# mainBoard.net
KiCad netlist of a schematic drawn in EAGLE
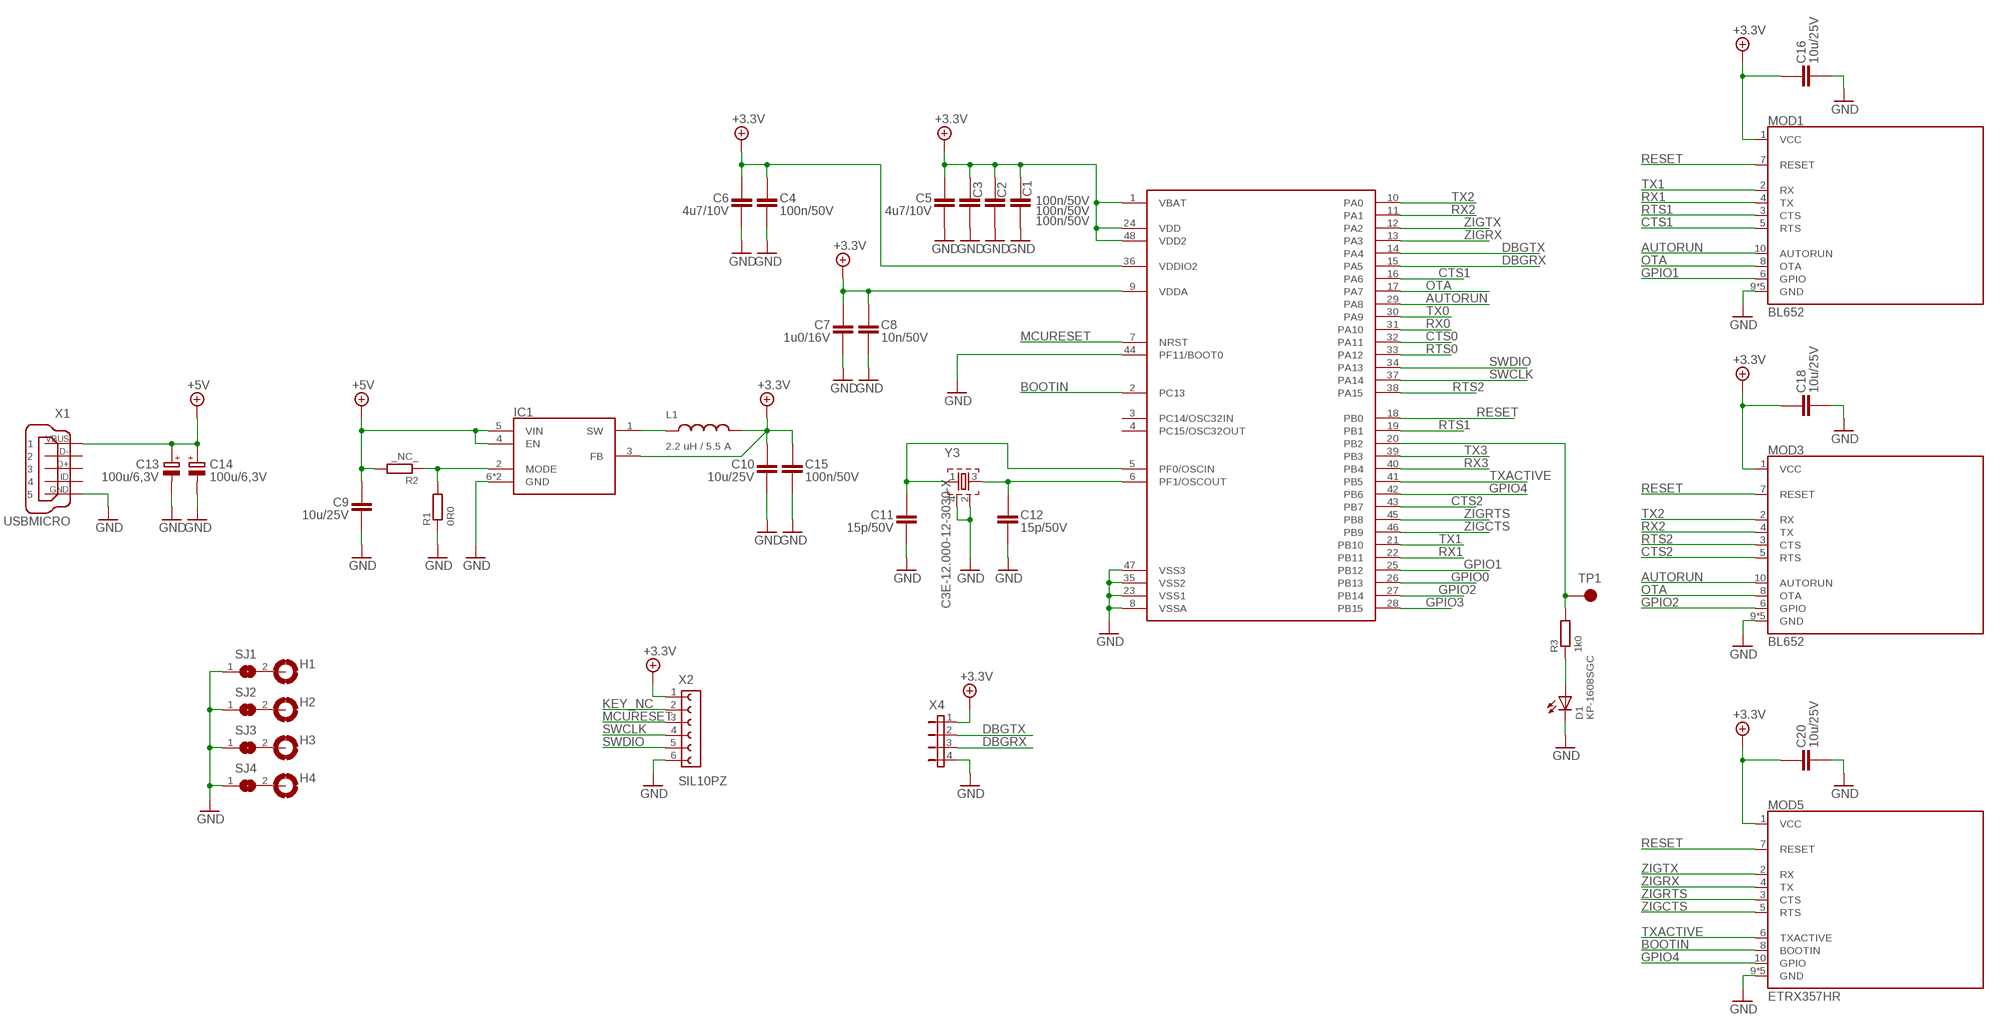
[diagram p0: schematic, sheet 1, part 1 of 2]
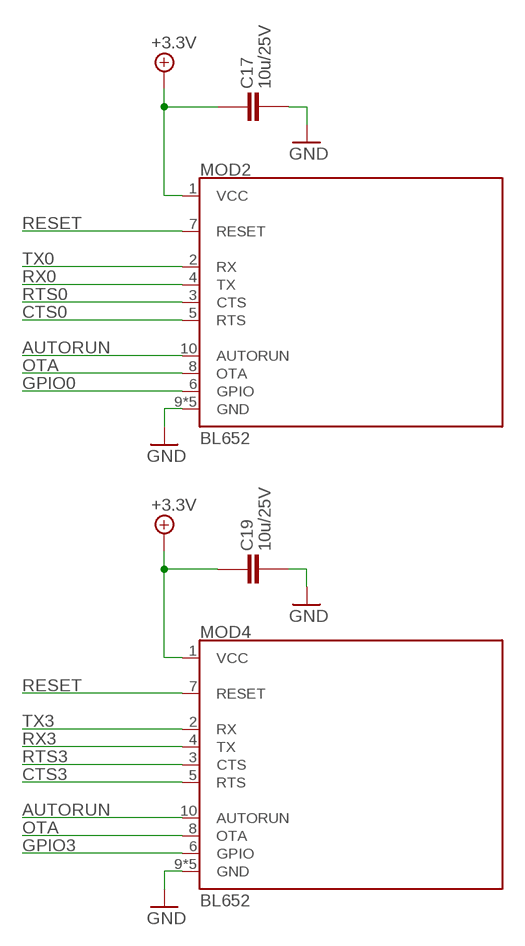
[diagram p1: schematic, sheet 1, part 2 of 2]

(export (version "E")
  (design (tool "Eeschema 10.0.6"))
  (components
    (comp (ref "C1")
      (value "100N/50V,X7R,+/-10%_0603R")
      (footprint "eagle-import:C0603R")
      (fields (field (name "COMPONENT_VALUE") "100n/50V"))
      (libsource (lib "eagle-import") (part "100N_0603R/50V,X7R,+/-10%"))
    )
    (comp (ref "C2")
      (value "100N/50V,X7R,+/-10%_0603R")
      (footprint "eagle-import:C0603R")
      (fields (field (name "COMPONENT_VALUE") "100n/50V"))
      (libsource (lib "eagle-import") (part "100N_0603R/50V,X7R,+/-10%"))
    )
    (comp (ref "C3")
      (value "100N/50V,X7R,+/-10%_0603R")
      (footprint "eagle-import:C0603R")
      (fields (field (name "COMPONENT_VALUE") "100n/50V"))
      (libsource (lib "eagle-import") (part "100N_0603R/50V,X7R,+/-10%"))
    )
    (comp (ref "C4")
      (value "100N/50V,X7R,+/-10%_0603R")
      (footprint "eagle-import:C0603R")
      (libsource (lib "eagle-import") (part "100N_0603R/50V,X7R,+/-10%"))
    )
    (comp (ref "C5")
      (value "4U7/10V,X5R,+/-10%_0603R")
      (footprint "eagle-import:C0603R")
      (libsource (lib "eagle-import") (part "4U7_0603R/10V,X5R,+/-10%"))
    )
    (comp (ref "C6")
      (value "4U7/10V,X5R,+/-10%_0603R")
      (footprint "eagle-import:C0603R")
      (libsource (lib "eagle-import") (part "4U7_0603R/10V,X5R,+/-10%"))
    )
    (comp (ref "C7")
      (value "1U0/16V,X5R,+/-10%_0603R")
      (footprint "eagle-import:C0603R")
      (libsource (lib "eagle-import") (part "1U0_0603R/16V,X5R,+/-10%"))
    )
    (comp (ref "C8")
      (value "10N/50V,X7R,+/-10%_0603R")
      (footprint "eagle-import:C0603R")
      (libsource (lib "eagle-import") (part "10N_0603R/50V,X7R,+/-10%"))
    )
    (comp (ref "C9")
      (value "10U/25V,X5R,+/-10%_0805R")
      (footprint "eagle-import:C0805R")
      (libsource (lib "eagle-import") (part "10U_0805R/25V,X5R,+/-10%"))
    )
    (comp (ref "C10")
      (value "10U/25V,X5R,+/-10%_0805R")
      (footprint "eagle-import:C0805R")
      (libsource (lib "eagle-import") (part "10U_0805R/25V,X5R,+/-10%"))
    )
    (comp (ref "C11")
      (value "15P/50V,COG/NPO,+/-5%_0603R")
      (footprint "eagle-import:C0603R")
      (libsource (lib "eagle-import") (part "15P_0603R/50V,COG/NPO,+/-5%"))
    )
    (comp (ref "C12")
      (value "15P/50V,COG/NPO,+/-5%_0603R")
      (footprint "eagle-import:C0603R")
      (libsource (lib "eagle-import") (part "15P_0603R/50V,COG/NPO,+/-5%"))
    )
    (comp (ref "C13")
      (value "100U")
      (footprint "eagle-import:CT6032")
      (libsource (lib "eagle-import") (part "100U"))
    )
    (comp (ref "C14")
      (value "100U")
      (footprint "eagle-import:CT6032")
      (libsource (lib "eagle-import") (part "100U"))
    )
    (comp (ref "C15")
      (value "100N/50V,X7R,+/-10%_0603R")
      (footprint "eagle-import:C0603R")
      (libsource (lib "eagle-import") (part "100N_0603R/50V,X7R,+/-10%"))
    )
    (comp (ref "C16")
      (value "10U/25V,X5R,+/-10%_0805R")
      (footprint "eagle-import:C0805R")
      (libsource (lib "eagle-import") (part "10U_0805R/25V,X5R,+/-10%"))
    )
    (comp (ref "C17")
      (value "10U/25V,X5R,+/-10%_0805R")
      (footprint "eagle-import:C0805R")
      (libsource (lib "eagle-import") (part "10U_0805R/25V,X5R,+/-10%"))
    )
    (comp (ref "C18")
      (value "10U/25V,X5R,+/-10%_0805R")
      (footprint "eagle-import:C0805R")
      (libsource (lib "eagle-import") (part "10U_0805R/25V,X5R,+/-10%"))
    )
    (comp (ref "C19")
      (value "10U/25V,X5R,+/-10%_0805R")
      (footprint "eagle-import:C0805R")
      (libsource (lib "eagle-import") (part "10U_0805R/25V,X5R,+/-10%"))
    )
    (comp (ref "C20")
      (value "10U/25V,X5R,+/-10%_0805R")
      (footprint "eagle-import:C0805R")
      (libsource (lib "eagle-import") (part "10U_0805R/25V,X5R,+/-10%"))
    )
    (comp (ref "D1")
      (value "KP-1608SGC")
      (footprint "eagle-import:0603")
      (libsource (lib "eagle-import") (part "KP-1608?SGC"))
    )
    (comp (ref "H1")
      (value "MOUNT-PAD-ROUND4.3")
      (footprint "eagle-import:4.3-PAD")
      (libsource (lib "eagle-import") (part "MOUNT-PAD-ROUND4.3"))
    )
    (comp (ref "H2")
      (value "MOUNT-PAD-ROUND4.3")
      (footprint "eagle-import:4.3-PAD")
      (libsource (lib "eagle-import") (part "MOUNT-PAD-ROUND4.3"))
    )
    (comp (ref "H3")
      (value "MOUNT-PAD-ROUND4.3")
      (footprint "eagle-import:4.3-PAD")
      (libsource (lib "eagle-import") (part "MOUNT-PAD-ROUND4.3"))
    )
    (comp (ref "H4")
      (value "MOUNT-PAD-ROUND4.3")
      (footprint "eagle-import:4.3-PAD")
      (libsource (lib "eagle-import") (part "MOUNT-PAD-ROUND4.3"))
    )
    (comp (ref "IC0")
      (value "STM32F091CCT")
      (footprint "eagle-import:LQFP48")
      (libsource (lib "eagle-import") (part "STM32F091CCT"))
    )
    (comp (ref "IC1")
      (value "TPS62291")
      (footprint "eagle-import:TPS62291")
      (libsource (lib "eagle-import") (part "TPS62291"))
    )
    (comp (ref "L1")
      (value "2U2_IHLP2020")
      (footprint "eagle-import:5.49X2X5.18MM")
      (libsource (lib "eagle-import") (part "2U2_IHLP2020"))
    )
    (comp (ref "MOD1")
      (value "BLEMODULE")
      (footprint "eagle-import:BLEMOD")
      (libsource (lib "eagle-import") (part "BLEMODULE"))
    )
    (comp (ref "MOD2")
      (value "BLEMODULE")
      (footprint "eagle-import:BLEMOD")
      (libsource (lib "eagle-import") (part "BLEMODULE"))
    )
    (comp (ref "MOD3")
      (value "BLEMODULE")
      (footprint "eagle-import:BLEMOD")
      (libsource (lib "eagle-import") (part "BLEMODULE"))
    )
    (comp (ref "MOD4")
      (value "BLEMODULE")
      (footprint "eagle-import:BLEMOD")
      (libsource (lib "eagle-import") (part "BLEMODULE"))
    )
    (comp (ref "MOD5")
      (value "ZIGBEE")
      (footprint "eagle-import:ZIGBEEMOD")
      (libsource (lib "eagle-import") (part "ZIGBEE"))
    )
    (comp (ref "R1")
      (value "0R0/0.1W,THICK_FILM,1%_0603R")
      (footprint "eagle-import:R0603R")
      (libsource (lib "eagle-import") (part "0R0_0603R/0.1W,THICK_FILM,1%"))
    )
    (comp (ref "R2")
      (value "_NC_/0.1W,THICK_FILM,1%_0603R")
      (footprint "eagle-import:R0603R")
      (libsource (lib "eagle-import") (part "_NC__0603R/0.1W,THICK_FILM,1%"))
    )
    (comp (ref "R3")
      (value "1K0/0.1W,THICK_FILM,1%_0603R")
      (footprint "eagle-import:R0603R")
      (libsource (lib "eagle-import") (part "1K0_0603R/0.1W,THICK_FILM,1%"))
    )
    (comp (ref "SJ1")
      (value "SJ_1-SMALL")
      (footprint "eagle-import:SJ-SMALL")
      (libsource (lib "eagle-import") (part "SJ_1?-SMALL"))
    )
    (comp (ref "SJ2")
      (value "SJ_1-SMALL")
      (footprint "eagle-import:SJ-SMALL")
      (libsource (lib "eagle-import") (part "SJ_1?-SMALL"))
    )
    (comp (ref "SJ3")
      (value "SJ_1-SMALL")
      (footprint "eagle-import:SJ-SMALL")
      (libsource (lib "eagle-import") (part "SJ_1?-SMALL"))
    )
    (comp (ref "SJ4")
      (value "SJ_1-SMALL")
      (footprint "eagle-import:SJ-SMALL")
      (libsource (lib "eagle-import") (part "SJ_1?-SMALL"))
    )
    (comp (ref "TP1")
      (value "TEST-PAD_3.5X2-SMD")
      (footprint "eagle-import:3.5X2_SMD")
      (libsource (lib "eagle-import") (part "TEST-PAD_3.5X2-SMD"))
    )
    (comp (ref "X1")
      (value "USBMICRO")
      (footprint "eagle-import:USBMICRO")
      (libsource (lib "eagle-import") (part "USBMICRO"))
    )
    (comp (ref "X2")
      (value "SOCKET_HADER-1X6")
      (footprint "eagle-import:1X06")
      (libsource (lib "eagle-import") (part "SOCKET_HADER-1X6"))
    )
    (comp (ref "X4")
      (value "PIN_HEADER-1X4")
      (footprint "eagle-import:1X04")
      (libsource (lib "eagle-import") (part "PIN_HEADER-1X4"))
    )
    (comp (ref "Y3")
      (value "C3E-12.000-12-3030-X")
      (footprint "eagle-import:3.4X2.7X0.75")
      (fields (field (name "COMPONENT_VALUE") "C3E-12.000-12-3030-X"))
      (libsource (lib "eagle-import") (part "C3E-12.000-12-3030-X"))
    )
  )
  (nets
    (net (code "1") (name "+3.3V") (class "Default")
      (node (ref "C1") (pin "2") (pinfunction "2_2") (pintype "passive"))
      (node (ref "C10") (pin "2") (pinfunction "2_2") (pintype "passive"))
      (node (ref "C15") (pin "2") (pinfunction "2_2") (pintype "passive"))
      (node (ref "C16") (pin "2") (pinfunction "2_2") (pintype "passive"))
      (node (ref "C17") (pin "2") (pinfunction "2_2") (pintype "passive"))
      (node (ref "C18") (pin "2") (pinfunction "2_2") (pintype "passive"))
      (node (ref "C19") (pin "2") (pinfunction "2_2") (pintype "passive"))
      (node (ref "C2") (pin "2") (pinfunction "2_2") (pintype "passive"))
      (node (ref "C20") (pin "2") (pinfunction "2_2") (pintype "passive"))
      (node (ref "C3") (pin "2") (pinfunction "2_2") (pintype "passive"))
      (node (ref "C4") (pin "2") (pinfunction "2_2") (pintype "passive"))
      (node (ref "C5") (pin "2") (pinfunction "2_2") (pintype "passive"))
      (node (ref "C6") (pin "2") (pinfunction "2_2") (pintype "passive"))
      (node (ref "C7") (pin "2") (pinfunction "2_2") (pintype "passive"))
      (node (ref "C8") (pin "2") (pinfunction "2_2") (pintype "passive"))
      (node (ref "IC0") (pin "1") (pinfunction "VBAT_1") (pintype "bidirectional"))
      (node (ref "IC0") (pin "24") (pinfunction "VDD_24") (pintype "bidirectional"))
      (node (ref "IC0") (pin "36") (pinfunction "VDDIO2_36") (pintype "bidirectional"))
      (node (ref "IC0") (pin "48") (pinfunction "VDD2_48") (pintype "bidirectional"))
      (node (ref "IC0") (pin "9") (pinfunction "VDDA_9") (pintype "bidirectional"))
      (node (ref "IC1") (pin "3") (pinfunction "FB_3") (pintype "bidirectional"))
      (node (ref "L1") (pin "P$2") (pinfunction "2_P$2") (pintype "passive"))
      (node (ref "MOD1") (pin "1") (pinfunction "VCC_1") (pintype "bidirectional"))
      (node (ref "MOD2") (pin "1") (pinfunction "VCC_1") (pintype "bidirectional"))
      (node (ref "MOD3") (pin "1") (pinfunction "VCC_1") (pintype "bidirectional"))
      (node (ref "MOD4") (pin "1") (pinfunction "VCC_1") (pintype "bidirectional"))
      (node (ref "MOD5") (pin "1") (pinfunction "VCC_1") (pintype "bidirectional"))
      (node (ref "X2") (pin "1") (pinfunction "1_1") (pintype "passive"))
      (node (ref "X4") (pin "1") (pinfunction "1_1") (pintype "passive"))
    )
    (net (code "2") (name "+5V") (class "Default")
      (node (ref "C13") (pin "+") (pinfunction "+_+") (pintype "passive"))
      (node (ref "C14") (pin "+") (pinfunction "+_+") (pintype "passive"))
      (node (ref "C9") (pin "2") (pinfunction "2_2") (pintype "passive"))
      (node (ref "IC1") (pin "4") (pinfunction "EN_4") (pintype "bidirectional"))
      (node (ref "IC1") (pin "5") (pinfunction "VIN_5") (pintype "bidirectional"))
      (node (ref "R2") (pin "2") (pinfunction "2_2") (pintype "passive"))
      (node (ref "X1") (pin "1") (pinfunction "1_1") (pintype "passive"))
    )
    (net (code "3") (name "/AUTORUN") (class "Default")
      (node (ref "IC0") (pin "29") (pinfunction "PA8_29") (pintype "bidirectional"))
      (node (ref "MOD1") (pin "10") (pinfunction "AUTORUN_10") (pintype "bidirectional"))
      (node (ref "MOD2") (pin "10") (pinfunction "AUTORUN_10") (pintype "bidirectional"))
      (node (ref "MOD3") (pin "10") (pinfunction "AUTORUN_10") (pintype "bidirectional"))
      (node (ref "MOD4") (pin "10") (pinfunction "AUTORUN_10") (pintype "bidirectional"))
    )
    (net (code "4") (name "/BOOTIN") (class "Default")
      (node (ref "IC0") (pin "2") (pinfunction "PC13_2") (pintype "bidirectional"))
      (node (ref "MOD5") (pin "8") (pinfunction "BOOTIN_8") (pintype "bidirectional"))
    )
    (net (code "5") (name "/CTS0") (class "Default")
      (node (ref "IC0") (pin "32") (pinfunction "PA11_32") (pintype "bidirectional"))
      (node (ref "MOD2") (pin "5") (pinfunction "RTS_5") (pintype "bidirectional"))
    )
    (net (code "6") (name "/CTS1") (class "Default")
      (node (ref "IC0") (pin "16") (pinfunction "PA6_16") (pintype "bidirectional"))
      (node (ref "MOD1") (pin "5") (pinfunction "RTS_5") (pintype "bidirectional"))
    )
    (net (code "7") (name "/CTS2") (class "Default")
      (node (ref "IC0") (pin "43") (pinfunction "PB7_43") (pintype "bidirectional"))
      (node (ref "MOD3") (pin "5") (pinfunction "RTS_5") (pintype "bidirectional"))
    )
    (net (code "8") (name "/CTS3") (class "Default")
      (node (ref "MOD4") (pin "5") (pinfunction "RTS_5") (pintype "bidirectional"))
    )
    (net (code "9") (name "/DBGRX") (class "Default")
      (node (ref "IC0") (pin "15") (pinfunction "PA5_15") (pintype "bidirectional"))
      (node (ref "X4") (pin "3") (pinfunction "3_3") (pintype "passive"))
    )
    (net (code "10") (name "/DBGTX") (class "Default")
      (node (ref "IC0") (pin "14") (pinfunction "PA4_14") (pintype "bidirectional"))
      (node (ref "X4") (pin "2") (pinfunction "2_2") (pintype "passive"))
    )
    (net (code "11") (name "/GPIO0") (class "Default")
      (node (ref "IC0") (pin "26") (pinfunction "PB13_26") (pintype "bidirectional"))
      (node (ref "MOD2") (pin "6") (pinfunction "GPIO_6") (pintype "bidirectional"))
    )
    (net (code "12") (name "/GPIO1") (class "Default")
      (node (ref "IC0") (pin "25") (pinfunction "PB12_25") (pintype "bidirectional"))
      (node (ref "MOD1") (pin "6") (pinfunction "GPIO_6") (pintype "bidirectional"))
    )
    (net (code "13") (name "/GPIO2") (class "Default")
      (node (ref "IC0") (pin "27") (pinfunction "PB14_27") (pintype "bidirectional"))
      (node (ref "MOD3") (pin "6") (pinfunction "GPIO_6") (pintype "bidirectional"))
    )
    (net (code "14") (name "/GPIO3") (class "Default")
      (node (ref "IC0") (pin "28") (pinfunction "PB15_28") (pintype "bidirectional"))
      (node (ref "MOD4") (pin "6") (pinfunction "GPIO_6") (pintype "bidirectional"))
    )
    (net (code "15") (name "/GPIO4") (class "Default")
      (node (ref "IC0") (pin "42") (pinfunction "PB6_42") (pintype "bidirectional"))
      (node (ref "MOD5") (pin "10") (pinfunction "GPIO_10") (pintype "bidirectional"))
    )
    (net (code "16") (name "/KEY_NC") (class "Default")
      (node (ref "X2") (pin "2") (pinfunction "2_2") (pintype "passive"))
    )
    (net (code "17") (name "/MCURESET") (class "Default")
      (node (ref "IC0") (pin "7") (pinfunction "NRST_7") (pintype "bidirectional"))
      (node (ref "X2") (pin "3") (pinfunction "3_3") (pintype "passive"))
    )
    (net (code "18") (name "/OTA") (class "Default")
      (node (ref "IC0") (pin "17") (pinfunction "PA7_17") (pintype "bidirectional"))
      (node (ref "MOD1") (pin "8") (pinfunction "OTA_8") (pintype "bidirectional"))
      (node (ref "MOD2") (pin "8") (pinfunction "OTA_8") (pintype "bidirectional"))
      (node (ref "MOD3") (pin "8") (pinfunction "OTA_8") (pintype "bidirectional"))
      (node (ref "MOD4") (pin "8") (pinfunction "OTA_8") (pintype "bidirectional"))
    )
    (net (code "19") (name "/RESET") (class "Default")
      (node (ref "IC0") (pin "18") (pinfunction "PB0_18") (pintype "bidirectional"))
      (node (ref "MOD1") (pin "7") (pinfunction "RESET_7") (pintype "bidirectional"))
      (node (ref "MOD2") (pin "7") (pinfunction "RESET_7") (pintype "bidirectional"))
      (node (ref "MOD3") (pin "7") (pinfunction "RESET_7") (pintype "bidirectional"))
      (node (ref "MOD4") (pin "7") (pinfunction "RESET_7") (pintype "bidirectional"))
      (node (ref "MOD5") (pin "7") (pinfunction "RESET_7") (pintype "bidirectional"))
    )
    (net (code "20") (name "/RTS0") (class "Default")
      (node (ref "IC0") (pin "33") (pinfunction "PA12_33") (pintype "bidirectional"))
      (node (ref "MOD2") (pin "3") (pinfunction "CTS_3") (pintype "bidirectional"))
    )
    (net (code "21") (name "/RTS1") (class "Default")
      (node (ref "IC0") (pin "19") (pinfunction "PB1_19") (pintype "bidirectional"))
      (node (ref "MOD1") (pin "3") (pinfunction "CTS_3") (pintype "bidirectional"))
    )
    (net (code "22") (name "/RTS2") (class "Default")
      (node (ref "IC0") (pin "38") (pinfunction "PA15_38") (pintype "bidirectional"))
      (node (ref "MOD3") (pin "3") (pinfunction "CTS_3") (pintype "bidirectional"))
    )
    (net (code "23") (name "/RTS3") (class "Default")
      (node (ref "MOD4") (pin "3") (pinfunction "CTS_3") (pintype "bidirectional"))
    )
    (net (code "24") (name "/RX0") (class "Default")
      (node (ref "IC0") (pin "31") (pinfunction "PA10_31") (pintype "bidirectional"))
      (node (ref "MOD2") (pin "4") (pinfunction "TX_4") (pintype "bidirectional"))
    )
    (net (code "25") (name "/RX1") (class "Default")
      (node (ref "IC0") (pin "22") (pinfunction "PB11_22") (pintype "bidirectional"))
      (node (ref "MOD1") (pin "4") (pinfunction "TX_4") (pintype "bidirectional"))
    )
    (net (code "26") (name "/RX2") (class "Default")
      (node (ref "IC0") (pin "11") (pinfunction "PA1_11") (pintype "bidirectional"))
      (node (ref "MOD3") (pin "4") (pinfunction "TX_4") (pintype "bidirectional"))
    )
    (net (code "27") (name "/RX3") (class "Default")
      (node (ref "IC0") (pin "40") (pinfunction "PB4_40") (pintype "bidirectional"))
      (node (ref "MOD4") (pin "4") (pinfunction "TX_4") (pintype "bidirectional"))
    )
    (net (code "28") (name "/SWCLK") (class "Default")
      (node (ref "IC0") (pin "37") (pinfunction "PA14_37") (pintype "bidirectional"))
      (node (ref "X2") (pin "4") (pinfunction "4_4") (pintype "passive"))
    )
    (net (code "29") (name "/SWDIO") (class "Default")
      (node (ref "IC0") (pin "34") (pinfunction "PA13_34") (pintype "bidirectional"))
      (node (ref "X2") (pin "5") (pinfunction "5_5") (pintype "passive"))
    )
    (net (code "30") (name "/TX0") (class "Default")
      (node (ref "IC0") (pin "30") (pinfunction "PA9_30") (pintype "bidirectional"))
      (node (ref "MOD2") (pin "2") (pinfunction "RX_2") (pintype "bidirectional"))
    )
    (net (code "31") (name "/TX1") (class "Default")
      (node (ref "IC0") (pin "21") (pinfunction "PB10_21") (pintype "bidirectional"))
      (node (ref "MOD1") (pin "2") (pinfunction "RX_2") (pintype "bidirectional"))
    )
    (net (code "32") (name "/TX2") (class "Default")
      (node (ref "IC0") (pin "10") (pinfunction "PA0_10") (pintype "bidirectional"))
      (node (ref "MOD3") (pin "2") (pinfunction "RX_2") (pintype "bidirectional"))
    )
    (net (code "33") (name "/TX3") (class "Default")
      (node (ref "IC0") (pin "39") (pinfunction "PB3_39") (pintype "bidirectional"))
      (node (ref "MOD4") (pin "2") (pinfunction "RX_2") (pintype "bidirectional"))
    )
    (net (code "34") (name "/TXACTIVE") (class "Default")
      (node (ref "IC0") (pin "41") (pinfunction "PB5_41") (pintype "bidirectional"))
      (node (ref "MOD5") (pin "6") (pinfunction "TXACTIVE_6") (pintype "bidirectional"))
    )
    (net (code "35") (name "/ZIGCTS") (class "Default")
      (node (ref "IC0") (pin "46") (pinfunction "PB9_46") (pintype "bidirectional"))
      (node (ref "MOD5") (pin "5") (pinfunction "RTS_5") (pintype "bidirectional"))
    )
    (net (code "36") (name "/ZIGRTS") (class "Default")
      (node (ref "IC0") (pin "45") (pinfunction "PB8_45") (pintype "bidirectional"))
      (node (ref "MOD5") (pin "3") (pinfunction "CTS_3") (pintype "bidirectional"))
    )
    (net (code "37") (name "/ZIGRX") (class "Default")
      (node (ref "IC0") (pin "13") (pinfunction "PA3_13") (pintype "bidirectional"))
      (node (ref "MOD5") (pin "4") (pinfunction "TX_4") (pintype "bidirectional"))
    )
    (net (code "38") (name "/ZIGTX") (class "Default")
      (node (ref "IC0") (pin "12") (pinfunction "PA2_12") (pintype "bidirectional"))
      (node (ref "MOD5") (pin "2") (pinfunction "RX_2") (pintype "bidirectional"))
    )
    (net (code "39") (name "GND") (class "Default")
      (node (ref "C1") (pin "1") (pinfunction "1_1") (pintype "passive"))
      (node (ref "C10") (pin "1") (pinfunction "1_1") (pintype "passive"))
      (node (ref "C11") (pin "1") (pinfunction "1_1") (pintype "passive"))
      (node (ref "C12") (pin "1") (pinfunction "1_1") (pintype "passive"))
      (node (ref "C13") (pin "-") (pinfunction "-_-") (pintype "passive"))
      (node (ref "C14") (pin "-") (pinfunction "-_-") (pintype "passive"))
      (node (ref "C15") (pin "1") (pinfunction "1_1") (pintype "passive"))
      (node (ref "C16") (pin "1") (pinfunction "1_1") (pintype "passive"))
      (node (ref "C17") (pin "1") (pinfunction "1_1") (pintype "passive"))
      (node (ref "C18") (pin "1") (pinfunction "1_1") (pintype "passive"))
      (node (ref "C19") (pin "1") (pinfunction "1_1") (pintype "passive"))
      (node (ref "C2") (pin "1") (pinfunction "1_1") (pintype "passive"))
      (node (ref "C20") (pin "1") (pinfunction "1_1") (pintype "passive"))
      (node (ref "C3") (pin "1") (pinfunction "1_1") (pintype "passive"))
      (node (ref "C4") (pin "1") (pinfunction "1_1") (pintype "passive"))
      (node (ref "C5") (pin "1") (pinfunction "1_1") (pintype "passive"))
      (node (ref "C6") (pin "1") (pinfunction "1_1") (pintype "passive"))
      (node (ref "C7") (pin "1") (pinfunction "1_1") (pintype "passive"))
      (node (ref "C8") (pin "1") (pinfunction "1_1") (pintype "passive"))
      (node (ref "C9") (pin "1") (pinfunction "1_1") (pintype "passive"))
      (node (ref "D1") (pin "2") (pinfunction "C_2") (pintype "passive"))
      (node (ref "IC0") (pin "23") (pinfunction "VSS1_23") (pintype "bidirectional"))
      (node (ref "IC0") (pin "35") (pinfunction "VSS2_35") (pintype "bidirectional"))
      (node (ref "IC0") (pin "44") (pinfunction "PF11/BOOT0_44") (pintype "bidirectional"))
      (node (ref "IC0") (pin "47") (pinfunction "VSS3_47") (pintype "bidirectional"))
      (node (ref "IC0") (pin "8") (pinfunction "VSSA_8") (pintype "bidirectional"))
      (node (ref "IC1") (pin "6") (pinfunction "GND_6") (pintype "bidirectional"))
      (node (ref "IC1") (pin "EXP") (pinfunction "GND_EXP") (pintype "bidirectional"))
      (node (ref "MOD1") (pin "9") (pinfunction "GND_9") (pintype "bidirectional"))
      (node (ref "MOD1") (pin "A1") (pinfunction "GND_A1") (pintype "bidirectional"))
      (node (ref "MOD1") (pin "A2") (pinfunction "GND_A2") (pintype "bidirectional"))
      (node (ref "MOD1") (pin "B1") (pinfunction "GND_B1") (pintype "bidirectional"))
      (node (ref "MOD1") (pin "B2") (pinfunction "GND_B2") (pintype "bidirectional"))
      (node (ref "MOD2") (pin "9") (pinfunction "GND_9") (pintype "bidirectional"))
      (node (ref "MOD2") (pin "A1") (pinfunction "GND_A1") (pintype "bidirectional"))
      (node (ref "MOD2") (pin "A2") (pinfunction "GND_A2") (pintype "bidirectional"))
      (node (ref "MOD2") (pin "B1") (pinfunction "GND_B1") (pintype "bidirectional"))
      (node (ref "MOD2") (pin "B2") (pinfunction "GND_B2") (pintype "bidirectional"))
      (node (ref "MOD3") (pin "9") (pinfunction "GND_9") (pintype "bidirectional"))
      (node (ref "MOD3") (pin "A1") (pinfunction "GND_A1") (pintype "bidirectional"))
      (node (ref "MOD3") (pin "A2") (pinfunction "GND_A2") (pintype "bidirectional"))
      (node (ref "MOD3") (pin "B1") (pinfunction "GND_B1") (pintype "bidirectional"))
      (node (ref "MOD3") (pin "B2") (pinfunction "GND_B2") (pintype "bidirectional"))
      (node (ref "MOD4") (pin "9") (pinfunction "GND_9") (pintype "bidirectional"))
      (node (ref "MOD4") (pin "A1") (pinfunction "GND_A1") (pintype "bidirectional"))
      (node (ref "MOD4") (pin "A2") (pinfunction "GND_A2") (pintype "bidirectional"))
      (node (ref "MOD4") (pin "B1") (pinfunction "GND_B1") (pintype "bidirectional"))
      (node (ref "MOD4") (pin "B2") (pinfunction "GND_B2") (pintype "bidirectional"))
      (node (ref "MOD5") (pin "9") (pinfunction "GND_9") (pintype "bidirectional"))
      (node (ref "MOD5") (pin "A1") (pinfunction "GND_A1") (pintype "bidirectional"))
      (node (ref "MOD5") (pin "A2") (pinfunction "GND_A2") (pintype "bidirectional"))
      (node (ref "MOD5") (pin "B1") (pinfunction "GND_B1") (pintype "bidirectional"))
      (node (ref "MOD5") (pin "B2") (pinfunction "GND_B2") (pintype "bidirectional"))
      (node (ref "R1") (pin "1") (pinfunction "1_1") (pintype "passive"))
      (node (ref "SJ1") (pin "1") (pinfunction "1_1") (pintype "passive"))
      (node (ref "SJ2") (pin "1") (pinfunction "1_1") (pintype "passive"))
      (node (ref "SJ3") (pin "1") (pinfunction "1_1") (pintype "passive"))
      (node (ref "SJ4") (pin "1") (pinfunction "1_1") (pintype "passive"))
      (node (ref "X1") (pin "5") (pinfunction "5_5") (pintype "passive"))
      (node (ref "X1") (pin "H1") (pinfunction "5_H1") (pintype "passive"))
      (node (ref "X1") (pin "H2") (pinfunction "5_H2") (pintype "passive"))
      (node (ref "X2") (pin "6") (pinfunction "6_6") (pintype "passive"))
      (node (ref "X4") (pin "4") (pinfunction "4_4") (pintype "passive"))
      (node (ref "Y3") (pin "2") (pinfunction "2_2") (pintype "passive"))
      (node (ref "Y3") (pin "4") (pinfunction "4_4") (pintype "passive"))
    )
    (net (code "40") (name "Net-(D1-A)") (class "Default")
      (node (ref "D1") (pin "1") (pinfunction "A_1") (pintype "passive"))
      (node (ref "R3") (pin "1") (pinfunction "1_1") (pintype "passive"))
    )
    (net (code "41") (name "Net-(H1-MOUNT)") (class "Default")
      (node (ref "H1") (pin "1") (pinfunction "MOUNT_1") (pintype "passive"))
      (node (ref "SJ1") (pin "2") (pinfunction "2_2") (pintype "passive"))
    )
    (net (code "42") (name "Net-(H2-MOUNT)") (class "Default")
      (node (ref "H2") (pin "1") (pinfunction "MOUNT_1") (pintype "passive"))
      (node (ref "SJ2") (pin "2") (pinfunction "2_2") (pintype "passive"))
    )
    (net (code "43") (name "Net-(H3-MOUNT)") (class "Default")
      (node (ref "H3") (pin "1") (pinfunction "MOUNT_1") (pintype "passive"))
      (node (ref "SJ3") (pin "2") (pinfunction "2_2") (pintype "passive"))
    )
    (net (code "44") (name "Net-(H4-MOUNT)") (class "Default")
      (node (ref "H4") (pin "1") (pinfunction "MOUNT_1") (pintype "passive"))
      (node (ref "SJ4") (pin "2") (pinfunction "2_2") (pintype "passive"))
    )
    (net (code "45") (name "Net-(IC0-PB2)") (class "Default")
      (node (ref "IC0") (pin "20") (pinfunction "PB2_20") (pintype "bidirectional"))
      (node (ref "R3") (pin "2") (pinfunction "2_2") (pintype "passive"))
      (node (ref "TP1") (pin "TP") (pinfunction "P$1_TP") (pintype "passive"))
    )
    (net (code "46") (name "Net-(IC0-PF0{slash}OSCIN)") (class "Default")
      (node (ref "C11") (pin "2") (pinfunction "2_2") (pintype "passive"))
      (node (ref "IC0") (pin "5") (pinfunction "PF0/OSCIN_5") (pintype "bidirectional"))
      (node (ref "Y3") (pin "1") (pinfunction "1_1") (pintype "passive"))
    )
    (net (code "47") (name "Net-(IC0-PF1{slash}OSCOUT)") (class "Default")
      (node (ref "C12") (pin "2") (pinfunction "2_2") (pintype "passive"))
      (node (ref "IC0") (pin "6") (pinfunction "PF1/OSCOUT_6") (pintype "bidirectional"))
      (node (ref "Y3") (pin "3") (pinfunction "3_3") (pintype "passive"))
    )
    (net (code "48") (name "Net-(IC1-MODE)") (class "Default")
      (node (ref "IC1") (pin "2") (pinfunction "MODE_2") (pintype "bidirectional"))
      (node (ref "R1") (pin "2") (pinfunction "2_2") (pintype "passive"))
      (node (ref "R2") (pin "1") (pinfunction "1_1") (pintype "passive"))
    )
    (net (code "49") (name "Net-(IC1-SW)") (class "Default")
      (node (ref "IC1") (pin "1") (pinfunction "SW_1") (pintype "bidirectional"))
      (node (ref "L1") (pin "P$1") (pinfunction "1_P$1") (pintype "passive"))
    )
    (net (code "50") (name "unconnected-(IC0-PC14{slash}OSC32IN-Pad3)") (class "Default")
      (node (ref "IC0") (pin "3") (pinfunction "PC14/OSC32IN_3") (pintype "bidirectional"))
    )
    (net (code "51") (name "unconnected-(IC0-PC15{slash}OSC32OUT-Pad4)") (class "Default")
      (node (ref "IC0") (pin "4") (pinfunction "PC15/OSC32OUT_4") (pintype "bidirectional"))
    )
    (net (code "52") (name "unconnected-(X1-Pad2)") (class "Default")
      (node (ref "X1") (pin "2") (pinfunction "2_2") (pintype "passive"))
    )
    (net (code "53") (name "unconnected-(X1-Pad3)") (class "Default")
      (node (ref "X1") (pin "3") (pinfunction "3_3") (pintype "passive"))
    )
    (net (code "54") (name "unconnected-(X1-Pad4)") (class "Default")
      (node (ref "X1") (pin "4") (pinfunction "4_4") (pintype "passive"))
    )
  )
)
